# TOP_VOLTAGE.net
KiCad netlist of a schematic drawn in Altium Designer
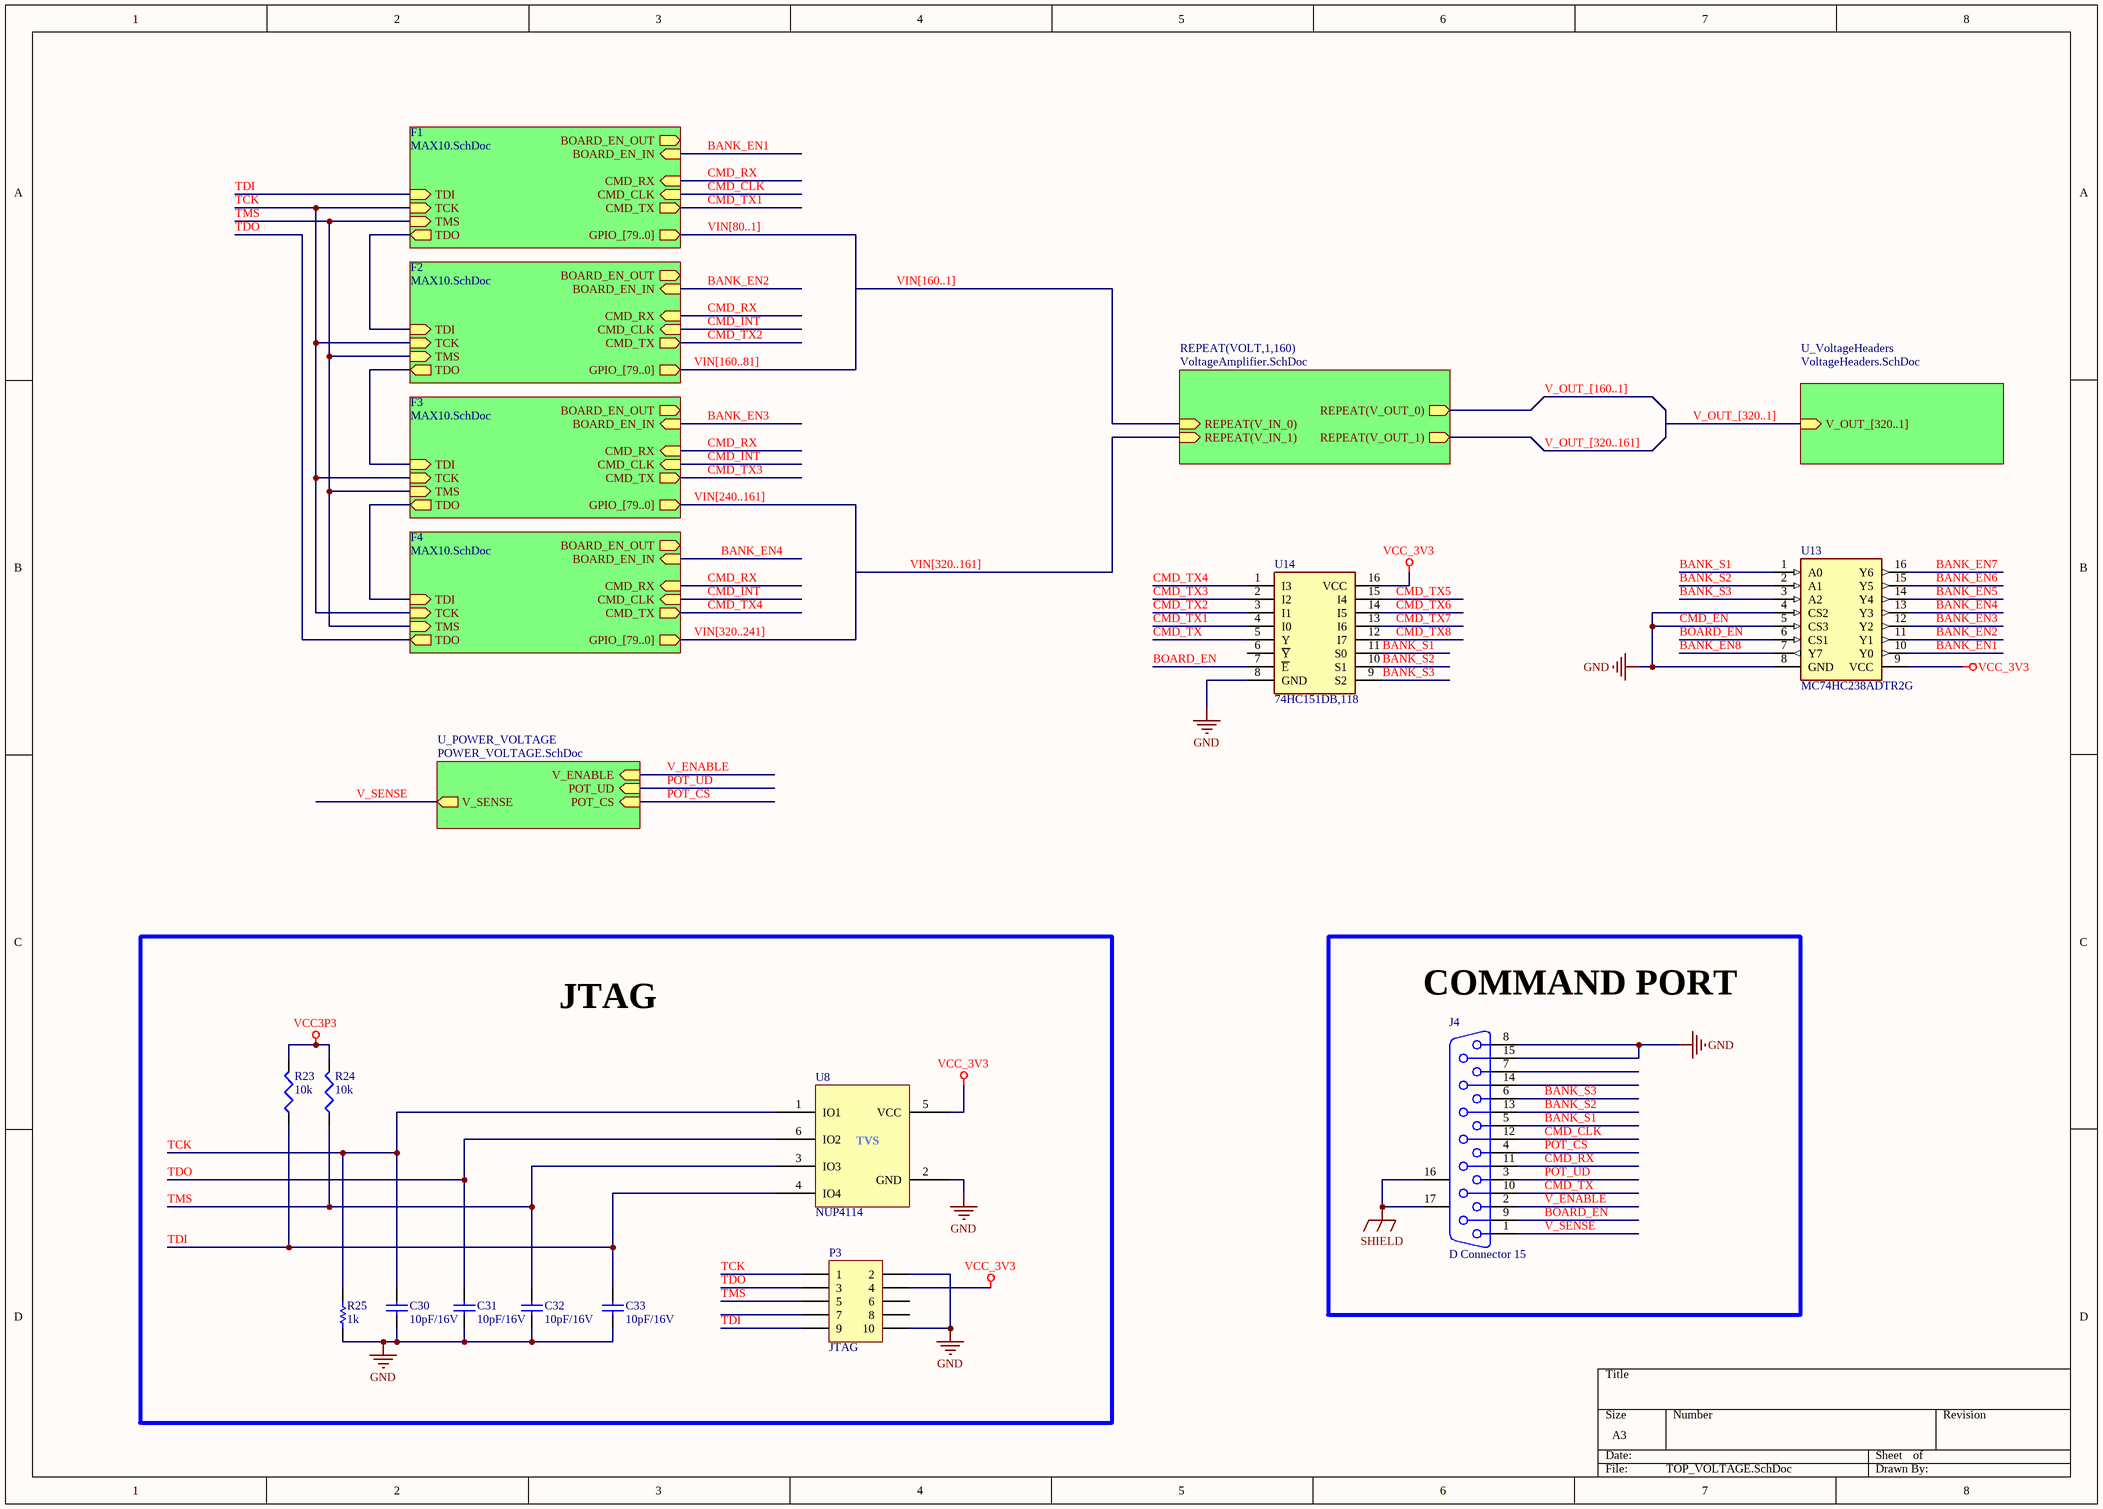
[diagram p0: TOP_VOLTAGE.SchDoc]

(export (version "E")
  (design (tool "Eeschema 10.0.6"))
  (components
    (comp (ref "C30")
      (value "10pF/16V")
      (footprint "0603_CAP")
      (description "Multilayer Ceramic Capacitors MLCC - SMD/SMT 16V 10pF 0603 X7R 0.1")
      (fields
        (field (name "STOCKIEST PART NO") "80-C0603C100K4RACTU")
        (field (name "MFR PART NO") "C0603C100K4RACTU")
      )
      (libsource (lib "Miscellaneous Devices") (part "Cap"))
    )
    (comp (ref "C31")
      (value "10pF/16V")
      (footprint "0603_CAP")
      (description "Multilayer Ceramic Capacitors MLCC - SMD/SMT 16V 10pF 0603 X7R 0.1")
      (fields
        (field (name "STOCKIEST PART NO") "80-C0603C100K4RACTU")
        (field (name "MFR PART NO") "C0603C100K4RACTU")
      )
      (libsource (lib "Miscellaneous Devices") (part "Cap"))
    )
    (comp (ref "C32")
      (value "10pF/16V")
      (footprint "0603_CAP")
      (description "Multilayer Ceramic Capacitors MLCC - SMD/SMT 16V 10pF 0603 X7R 0.1")
      (fields
        (field (name "STOCKIEST PART NO") "80-C0603C100K4RACTU")
        (field (name "MFR PART NO") "C0603C100K4RACTU")
      )
      (libsource (lib "Miscellaneous Devices") (part "Cap"))
    )
    (comp (ref "C33")
      (value "10pF/16V")
      (footprint "0603_CAP")
      (description "Multilayer Ceramic Capacitors MLCC - SMD/SMT 16V 10pF 0603 X7R 0.1")
      (fields
        (field (name "STOCKIEST PART NO") "80-C0603C100K4RACTU")
        (field (name "MFR PART NO") "C0603C100K4RACTU")
      )
      (libsource (lib "Miscellaneous Devices") (part "Cap"))
    )
    (comp (ref "J4")
      (value "D Connector 15")
      (footprint "DSUB1.385-2H15")
      (description "Receptacle Assembly, 15 Position, Right Angle")
      (fields (field (name "PUBLISHER") "Altium Limited"))
      (libsource (lib "Miscellaneous Connectors") (part "D Connector 15"))
    )
    (comp (ref "P3")
      (value "JTAG")
      (footprint "HDR2X5")
      (description "Header, 5-Pin, Dual row")
      (fields (field (name "PUBLISHER") "Altium Limited"))
      (libsource (lib "Miscellaneous Connectors") (part "Header 5X2"))
    )
    (comp (ref "R23")
      (value "10k")
      (footprint "0402_RES")
      (description "Thick Film Resistors - SMD 10K OHM 1%")
      (fields (field (name "MANUFACTURER") "Yageo") (field (name "STOCKIEST PART NO") "603-RC0402FR-0710KL"))
      (libsource (lib "altium-import") (part "root_1_0402_RES_"))
    )
    (comp (ref "R24")
      (value "10k")
      (footprint "0402_RES")
      (description "Thick Film Resistors - SMD 10K OHM 1%")
      (fields (field (name "MANUFACTURER") "Yageo") (field (name "STOCKIEST PART NO") "603-RC0402FR-0710KL"))
      (libsource (lib "altium-import") (part "root_1_0402_RES_"))
    )
    (comp (ref "R25")
      (value "1k")
      (footprint "RES_0805")
      (description "Thick Film Resistors - SMD 1/16W 1K Ohm 50V 1% ANTI SULFUR AEC-Q200")
      (fields
        (field (name "STOCKIEST PART NO") "603-AA0402FR-071KL")
        (field (name "MFR PART NO") "AA0402FR-071KL")
      )
      (libsource (lib "Miscellaneous Devices") (part "Res1"))
    )
    (comp (ref "U8")
      (value "NUP4114")
      (footprint "NUP4114HMR6T1G")
      (description "ESD Suppressors / TVS Diodes LOW CAP TVS ARRAY 5.5V")
      (fields
        (field (name "MFR PART NO") "NUP4114HMR6T1G")
        (field (name "STOCKIEST PART NO") "863-NUP4114HMR6T1G")
      )
      (libsource (lib "Schlib1") (part "NUP4114"))
    )
    (comp (ref "U13")
      (value "MC74HC238ADTR2G")
      (footprint "SamacSys:SOP65P640X120-16N")
      (description "Integrated Circuit")
      (fields (field (name "MOUSER PART NUMBER") "863-MC74HC238ADTR2G"))
      (libsource (lib "*") (part "MC74HC238ADTR2G"))
    )
    (comp (ref "U14")
      (value "74HC151DB,118")
      (footprint "SamacSys:SOP65P775X200-16N")
      (description "Integrated Circuit")
      (fields (field (name "MOUSER PART NUMBER") "771-HC151DB118"))
      (libsource (lib "*") (part "74HC151DB,118"))
    )
  )
  (nets
    (net (code "401") (name "/BANK_EN1") (class "Default")
      (node (ref "U13") (pin "10") (pinfunction "Y0_10") (pintype "output"))
    )
    (net (code "402") (name "/BANK_EN2") (class "Default")
      (node (ref "U13") (pin "11") (pinfunction "Y1_11") (pintype "output"))
    )
    (net (code "403") (name "/BANK_EN3") (class "Default")
      (node (ref "U13") (pin "12") (pinfunction "Y2_12") (pintype "output"))
    )
    (net (code "404") (name "/BANK_EN4") (class "Default")
      (node (ref "U13") (pin "13") (pinfunction "Y3_13") (pintype "output"))
    )
    (net (code "405") (name "/BANK_EN5") (class "Default")
      (node (ref "U13") (pin "14") (pinfunction "Y4_14") (pintype "output"))
    )
    (net (code "406") (name "/BANK_EN6") (class "Default")
      (node (ref "U13") (pin "15") (pinfunction "Y5_15") (pintype "output"))
    )
    (net (code "407") (name "/BANK_EN7") (class "Default")
      (node (ref "U13") (pin "16") (pinfunction "Y6_16") (pintype "output"))
    )
    (net (code "408") (name "/BANK_EN8") (class "Default")
      (node (ref "U13") (pin "7") (pinfunction "Y7_7") (pintype "output"))
    )
    (net (code "409") (name "/BANK_S1") (class "Default")
      (node (ref "J4") (pin "5") (pinfunction "5_5") (pintype "passive"))
      (node (ref "U13") (pin "1") (pinfunction "A0_1") (pintype "input"))
      (node (ref "U14") (pin "11") (pinfunction "S0_11") (pintype "passive"))
    )
    (net (code "410") (name "/BANK_S2") (class "Default")
      (node (ref "J4") (pin "13") (pinfunction "13_13") (pintype "passive"))
      (node (ref "U13") (pin "2") (pinfunction "A1_2") (pintype "input"))
      (node (ref "U14") (pin "10") (pinfunction "S1_10") (pintype "passive"))
    )
    (net (code "411") (name "/BANK_S3") (class "Default")
      (node (ref "J4") (pin "6") (pinfunction "6_6") (pintype "passive"))
      (node (ref "U13") (pin "3") (pinfunction "A2_3") (pintype "input"))
      (node (ref "U14") (pin "9") (pinfunction "S2_9") (pintype "passive"))
    )
    (net (code "412") (name "/BOARD_EN") (class "Default")
      (node (ref "J4") (pin "9") (pinfunction "9_9") (pintype "passive"))
      (node (ref "U13") (pin "6") (pinfunction "CS1_6") (pintype "input"))
      (node (ref "U14") (pin "7") (pinfunction "~{E}_7") (pintype "passive"))
    )
    (net (code "417") (name "/CMD_CLK") (class "Default")
      (node (ref "J4") (pin "12") (pinfunction "12_12") (pintype "passive"))
    )
    (net (code "419") (name "/CMD_RX") (class "Default")
      (node (ref "J4") (pin "11") (pinfunction "11_11") (pintype "passive"))
    )
    (net (code "420") (name "/CMD_TX") (class "Default")
      (node (ref "J4") (pin "10") (pinfunction "10_10") (pintype "passive"))
      (node (ref "U14") (pin "5") (pinfunction "Y_5") (pintype "passive"))
    )
    (net (code "421") (name "/CMD_TX1") (class "Default")
      (node (ref "U14") (pin "4") (pinfunction "I0_4") (pintype "passive"))
    )
    (net (code "422") (name "/CMD_TX2") (class "Default")
      (node (ref "U14") (pin "3") (pinfunction "I1_3") (pintype "passive"))
    )
    (net (code "423") (name "/CMD_TX3") (class "Default")
      (node (ref "U14") (pin "2") (pinfunction "I2_2") (pintype "passive"))
    )
    (net (code "424") (name "/CMD_TX4") (class "Default")
      (node (ref "U14") (pin "1") (pinfunction "I3_1") (pintype "passive"))
    )
    (net (code "425") (name "/CMD_TX5") (class "Default")
      (node (ref "U14") (pin "15") (pinfunction "I4_15") (pintype "passive"))
    )
    (net (code "426") (name "/CMD_TX6") (class "Default")
      (node (ref "U14") (pin "14") (pinfunction "I5_14") (pintype "passive"))
    )
    (net (code "427") (name "/CMD_TX7") (class "Default")
      (node (ref "U14") (pin "13") (pinfunction "I6_13") (pintype "passive"))
    )
    (net (code "428") (name "/CMD_TX8") (class "Default")
      (node (ref "U14") (pin "12") (pinfunction "I7_12") (pintype "passive"))
    )
    (net (code "429") (name "/POT_CS") (class "Default")
      (node (ref "J4") (pin "4") (pinfunction "4_4") (pintype "passive"))
    )
    (net (code "430") (name "/POT_UD") (class "Default")
      (node (ref "J4") (pin "3") (pinfunction "3_3") (pintype "passive"))
    )
    (net (code "433") (name "/TCK") (class "Default")
      (node (ref "C30") (pin "2") (pinfunction "2_2") (pintype "passive"))
      (node (ref "P3") (pin "1") (pinfunction "1_1") (pintype "passive"))
      (node (ref "R25") (pin "1") (pinfunction "1_1") (pintype "passive"))
      (node (ref "U8") (pin "1") (pinfunction "IO1_1") (pintype "passive"))
    )
    (net (code "434") (name "/TDI") (class "Default")
      (node (ref "C33") (pin "2") (pinfunction "2_2") (pintype "passive"))
      (node (ref "P3") (pin "9") (pinfunction "9_9") (pintype "passive"))
      (node (ref "R23") (pin "1") (pinfunction "1_1") (pintype "passive"))
      (node (ref "U8") (pin "4") (pinfunction "IO4_4") (pintype "passive"))
    )
    (net (code "435") (name "/TDO") (class "Default")
      (node (ref "C31") (pin "2") (pinfunction "2_2") (pintype "passive"))
      (node (ref "P3") (pin "3") (pinfunction "3_3") (pintype "passive"))
      (node (ref "U8") (pin "6") (pinfunction "IO2_6") (pintype "passive"))
    )
    (net (code "439") (name "/TMS") (class "Default")
      (node (ref "C32") (pin "2") (pinfunction "2_2") (pintype "passive"))
      (node (ref "P3") (pin "5") (pinfunction "5_5") (pintype "passive"))
      (node (ref "R24") (pin "1") (pinfunction "1_1") (pintype "passive"))
      (node (ref "U8") (pin "3") (pinfunction "IO3_3") (pintype "passive"))
    )
    (net (code "442") (name "/V_ENABLE") (class "Default")
      (node (ref "J4") (pin "2") (pinfunction "2_2") (pintype "passive"))
    )
    (net (code "444") (name "/V_SENSE") (class "Default")
      (node (ref "J4") (pin "1") (pinfunction "1_1") (pintype "passive"))
    )
    (net (code "445") (name "GND") (class "Default")
      (node (ref "C30") (pin "1") (pinfunction "1_1") (pintype "passive"))
      (node (ref "C31") (pin "1") (pinfunction "1_1") (pintype "passive"))
      (node (ref "C32") (pin "1") (pinfunction "1_1") (pintype "passive"))
      (node (ref "C33") (pin "1") (pinfunction "1_1") (pintype "passive"))
      (node (ref "J4") (pin "15") (pinfunction "15_15") (pintype "passive"))
      (node (ref "J4") (pin "8") (pinfunction "8_8") (pintype "passive"))
      (node (ref "P3") (pin "10") (pinfunction "10_10") (pintype "passive"))
      (node (ref "P3") (pin "2") (pinfunction "2_2") (pintype "passive"))
      (node (ref "R25") (pin "2") (pinfunction "2_2") (pintype "passive"))
      (node (ref "U13") (pin "4") (pinfunction "CS2_4") (pintype "input"))
      (node (ref "U13") (pin "5") (pinfunction "CS3_5") (pintype "input"))
      (node (ref "U13") (pin "8") (pinfunction "GND_8") (pintype "power_in"))
      (node (ref "U14") (pin "8") (pinfunction "GND_8") (pintype "passive"))
      (node (ref "U8") (pin "2") (pinfunction "GND_2") (pintype "passive"))
    )
    (net (code "446") (name "SHIELD") (class "Default")
      (node (ref "J4") (pin "16") (pinfunction "MH1_16") (pintype "passive"))
      (node (ref "J4") (pin "17") (pinfunction "MH2_17") (pintype "passive"))
    )
    (net (code "447") (name "VCC3P3") (class "Default")
      (node (ref "R23") (pin "2") (pinfunction "2_2") (pintype "passive"))
      (node (ref "R24") (pin "2") (pinfunction "2_2") (pintype "passive"))
    )
    (net (code "448") (name "VCC_3V3") (class "Default")
      (node (ref "P3") (pin "4") (pinfunction "4_4") (pintype "passive"))
      (node (ref "U13") (pin "9") (pinfunction "VCC_9") (pintype "power_in"))
      (node (ref "U14") (pin "16") (pinfunction "VCC_16") (pintype "passive"))
      (node (ref "U8") (pin "5") (pinfunction "VCC_5") (pintype "passive"))
    )
    (net (code "449") (name "unconnected-(J4-Pad7)") (class "Default")
      (node (ref "J4") (pin "7") (pinfunction "7_7") (pintype "passive"))
    )
    (net (code "450") (name "unconnected-(J4-Pad14)") (class "Default")
      (node (ref "J4") (pin "14") (pinfunction "14_14") (pintype "passive"))
    )
    (net (code "451") (name "unconnected-(P3-Pad6)") (class "Default")
      (node (ref "P3") (pin "6") (pinfunction "6_6") (pintype "passive"))
    )
    (net (code "452") (name "unconnected-(P3-Pad7)") (class "Default")
      (node (ref "P3") (pin "7") (pinfunction "7_7") (pintype "passive"))
    )
    (net (code "453") (name "unconnected-(P3-Pad8)") (class "Default")
      (node (ref "P3") (pin "8") (pinfunction "8_8") (pintype "passive"))
    )
    (net (code "454") (name "unconnected-(U14-~{Y}-Pad6)") (class "Default")
      (node (ref "U14") (pin "6") (pinfunction "~{Y}_6") (pintype "passive"))
    )
  )
)
